# Test.net
KiCad netlist of a schematic drawn in EAGLE
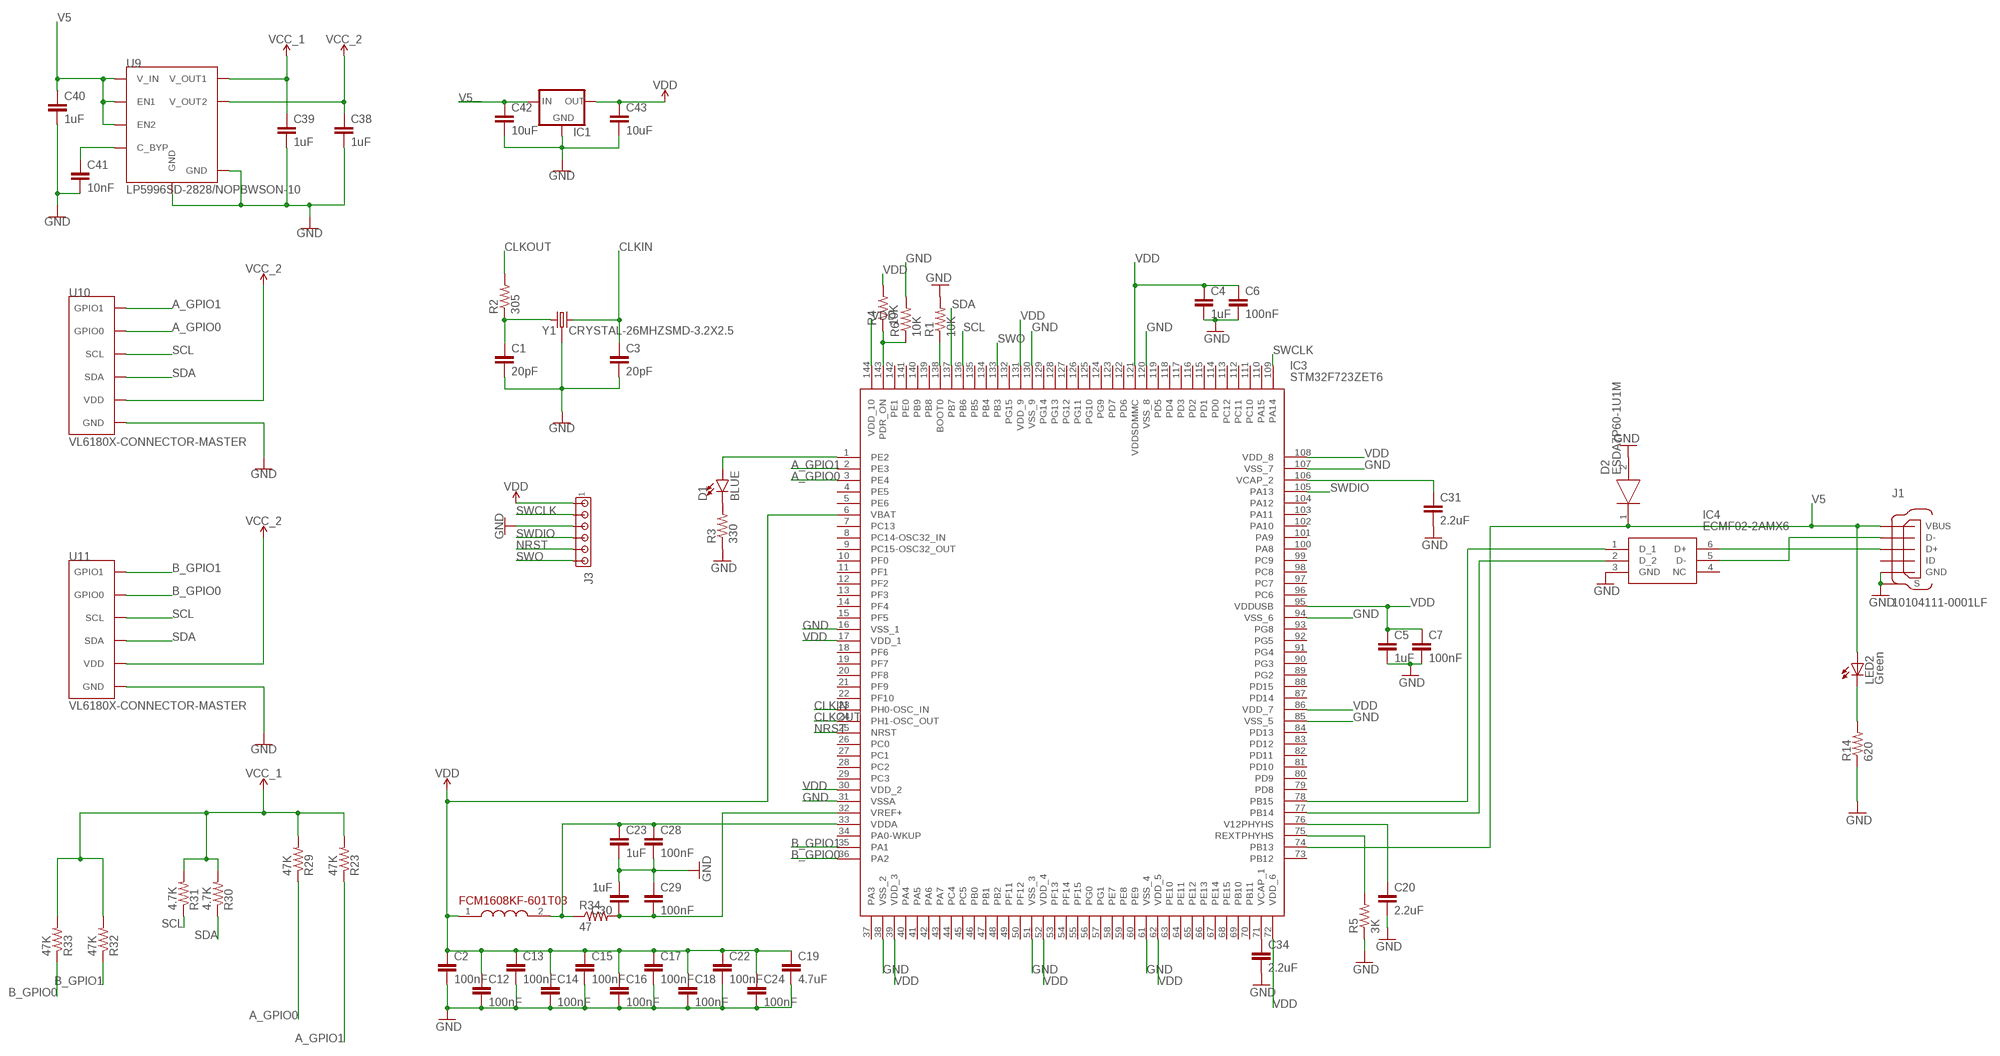
[diagram p0: schematic, sheet 1]

(export (version "E")
  (design (tool "Eeschema 10.0.6"))
  (components
    (comp (ref "C1")
      (value "20pF")
      (footprint "eagle-import:C0603")
      (libsource (lib "eagle-import") (part "C-EUC0603"))
    )
    (comp (ref "C2")
      (value "100nF")
      (footprint "eagle-import:C0603K")
      (libsource (lib "eagle-import") (part "C-EUC0603K"))
    )
    (comp (ref "C3")
      (value "20pF")
      (footprint "eagle-import:C0603")
      (libsource (lib "eagle-import") (part "C-EUC0603"))
    )
    (comp (ref "C4")
      (value "1uF")
      (footprint "eagle-import:C0603K")
      (libsource (lib "eagle-import") (part "C-EUC0603K"))
    )
    (comp (ref "C5")
      (value "1uF")
      (footprint "eagle-import:C0603K")
      (libsource (lib "eagle-import") (part "C-EUC0603K"))
    )
    (comp (ref "C6")
      (value "100nF")
      (footprint "eagle-import:C0603K")
      (libsource (lib "eagle-import") (part "C-EUC0603K"))
    )
    (comp (ref "C7")
      (value "100nF")
      (footprint "eagle-import:C0603K")
      (libsource (lib "eagle-import") (part "C-EUC0603K"))
    )
    (comp (ref "C12")
      (value "100nF")
      (footprint "eagle-import:C0603K")
      (libsource (lib "eagle-import") (part "C-EUC0603K"))
    )
    (comp (ref "C13")
      (value "100nF")
      (footprint "eagle-import:C0603K")
      (libsource (lib "eagle-import") (part "C-EUC0603K"))
    )
    (comp (ref "C14")
      (value "100nF")
      (footprint "eagle-import:C0603K")
      (libsource (lib "eagle-import") (part "C-EUC0603K"))
    )
    (comp (ref "C15")
      (value "100nF")
      (footprint "eagle-import:C0603K")
      (libsource (lib "eagle-import") (part "C-EUC0603K"))
    )
    (comp (ref "C16")
      (value "100nF")
      (footprint "eagle-import:C0603K")
      (libsource (lib "eagle-import") (part "C-EUC0603K"))
    )
    (comp (ref "C17")
      (value "100nF")
      (footprint "eagle-import:C0603K")
      (libsource (lib "eagle-import") (part "C-EUC0603K"))
    )
    (comp (ref "C18")
      (value "100nF")
      (footprint "eagle-import:C0603K")
      (libsource (lib "eagle-import") (part "C-EUC0603K"))
    )
    (comp (ref "C19")
      (value "4.7uF")
      (footprint "eagle-import:C0603K")
      (libsource (lib "eagle-import") (part "C-EUC0603K"))
    )
    (comp (ref "C20")
      (value "2.2uF")
      (footprint "eagle-import:C0603K")
      (libsource (lib "eagle-import") (part "C-EUC0603K"))
    )
    (comp (ref "C22")
      (value "100nF")
      (footprint "eagle-import:C0603K")
      (libsource (lib "eagle-import") (part "C-EUC0603K"))
    )
    (comp (ref "C23")
      (value "1uF")
      (footprint "eagle-import:C0603K")
      (libsource (lib "eagle-import") (part "C-EUC0603K"))
    )
    (comp (ref "C24")
      (value "100nF")
      (footprint "eagle-import:C0603K")
      (libsource (lib "eagle-import") (part "C-EUC0603K"))
    )
    (comp (ref "C28")
      (value "100nF")
      (footprint "eagle-import:C0603K")
      (libsource (lib "eagle-import") (part "C-EUC0603K"))
    )
    (comp (ref "C29")
      (value "100nF")
      (footprint "eagle-import:C0603K")
      (libsource (lib "eagle-import") (part "C-EUC0603K"))
    )
    (comp (ref "C30")
      (value "1uF")
      (footprint "eagle-import:C0603K")
      (libsource (lib "eagle-import") (part "C-EUC0603K"))
    )
    (comp (ref "C31")
      (value "2.2uF")
      (footprint "eagle-import:C0603K")
      (libsource (lib "eagle-import") (part "C-EUC0603K"))
    )
    (comp (ref "C34")
      (value "2.2uF")
      (footprint "eagle-import:C0603K")
      (libsource (lib "eagle-import") (part "C-EUC0603K"))
    )
    (comp (ref "C38")
      (value "1uF")
      (footprint "eagle-import:C0603K")
      (libsource (lib "eagle-import") (part "C-EUC0603K"))
    )
    (comp (ref "C39")
      (value "1uF")
      (footprint "eagle-import:C0603K")
      (libsource (lib "eagle-import") (part "C-EUC0603K"))
    )
    (comp (ref "C40")
      (value "1uF")
      (footprint "eagle-import:C0603K")
      (libsource (lib "eagle-import") (part "C-EUC0603K"))
    )
    (comp (ref "C41")
      (value "10nF")
      (footprint "eagle-import:C0603K")
      (libsource (lib "eagle-import") (part "C-EUC0603K"))
    )
    (comp (ref "C42")
      (value "10uF")
      (footprint "eagle-import:C0603K")
      (libsource (lib "eagle-import") (part "C-EUC0603K"))
    )
    (comp (ref "C43")
      (value "10uF")
      (footprint "eagle-import:C0603K")
      (libsource (lib "eagle-import") (part "C-EUC0603K"))
    )
    (comp (ref "D1")
      (value "BLUE")
      (footprint "eagle-import:LED-0603")
      (libsource (lib "eagle-import") (part "LED-BLUE0603"))
    )
    (comp (ref "D2")
      (value "ESDA7P60-1U1M")
      (footprint "eagle-import:ESDA7P601U1M")
      (fields (field (name "MOUSER_PART_NUMBER") "511-ESDA7P60-1U1M"))
      (libsource (lib "eagle-import") (part "ESDA7P60-1U1M"))
    )
    (comp (ref "FCM1608KF")
      (value "FCM1608KF-601T03")
      (footprint "eagle-import:FCM1608KF-601T03")
      (libsource (lib "eagle-import") (part "FCM1608KF-601T03"))
    )
    (comp (ref "IC1")
      (value "LM1117")
      (footprint "eagle-import:SOT223")
      (libsource (lib "eagle-import") (part "LM1117"))
    )
    (comp (ref "IC3")
      (value "STM32F723ZET6")
      (footprint "eagle-import:QFP50P2200X2200X160-144N")
      (fields (field (name "MOUSER_PART_NUMBER") "511-STM32F723ZET6"))
      (libsource (lib "eagle-import") (part "STM32F723ZET6"))
    )
    (comp (ref "IC4")
      (value "ECMF02-2AMX6")
      (footprint "eagle-import:SON50P150X170X55-6N")
      (fields (field (name "MOUSER_PART_NUMBER") "511-ECMF02-2AMX6"))
      (libsource (lib "eagle-import") (part "ECMF02-2AMX6"))
    )
    (comp (ref "J1")
      (value "10104111-0001LF")
      (footprint "eagle-import:FRAMATOME_10104111-0001LF")
      (fields (field (name "MF") "Amphenol ICC"))
      (libsource (lib "eagle-import") (part "10104111-0001LF"))
    )
    (comp (ref "J3")
      (value "MTA06-100")
      (footprint "eagle-import:10X06MTA")
      (libsource (lib "eagle-import") (part "MTA06-100"))
    )
    (comp (ref "LED2")
      (value "Green")
      (footprint "eagle-import:CHIP-LED0603")
      (libsource (lib "eagle-import") (part "LEDCHIP-LED0603"))
    )
    (comp (ref "R1")
      (value "10K")
      (footprint "eagle-import:R0603")
      (libsource (lib "eagle-import") (part "R-US_R0603"))
    )
    (comp (ref "R2")
      (value "305")
      (footprint "eagle-import:R0603")
      (libsource (lib "eagle-import") (part "R-US_R0603"))
    )
    (comp (ref "R3")
      (value "330")
      (footprint "eagle-import:R0603")
      (libsource (lib "eagle-import") (part "R-US_R0603"))
    )
    (comp (ref "R4")
      (value "10K")
      (footprint "eagle-import:R0603")
      (libsource (lib "eagle-import") (part "R-US_R0603"))
    )
    (comp (ref "R5")
      (value "3K")
      (footprint "eagle-import:R0603")
      (libsource (lib "eagle-import") (part "R-US_R0603"))
    )
    (comp (ref "R6")
      (value "10K")
      (footprint "eagle-import:R0603")
      (libsource (lib "eagle-import") (part "R-US_R0603"))
    )
    (comp (ref "R14")
      (value "620")
      (footprint "eagle-import:R0603")
      (libsource (lib "eagle-import") (part "R-US_R0603"))
    )
    (comp (ref "R23")
      (value "47K")
      (footprint "eagle-import:R0603")
      (libsource (lib "eagle-import") (part "R-US_R0603"))
    )
    (comp (ref "R29")
      (value "47K")
      (footprint "eagle-import:R0603")
      (libsource (lib "eagle-import") (part "R-US_R0603"))
    )
    (comp (ref "R30")
      (value "4.7K")
      (footprint "eagle-import:R0603")
      (libsource (lib "eagle-import") (part "R-US_R0603"))
    )
    (comp (ref "R31")
      (value "4.7K")
      (footprint "eagle-import:R0603")
      (libsource (lib "eagle-import") (part "R-US_R0603"))
    )
    (comp (ref "R32")
      (value "47K")
      (footprint "eagle-import:R0603")
      (libsource (lib "eagle-import") (part "R-US_R0603"))
    )
    (comp (ref "R33")
      (value "47K")
      (footprint "eagle-import:R0603")
      (libsource (lib "eagle-import") (part "R-US_R0603"))
    )
    (comp (ref "R34")
      (value "47")
      (footprint "eagle-import:R0603")
      (libsource (lib "eagle-import") (part "R-US_R0603"))
    )
    (comp (ref "U9")
      (value "LP5996SD-2828/NOPBWSON-10")
      (footprint "eagle-import:WSON-10")
      (libsource (lib "eagle-import") (part "LP5996SD-2828/NOPBWSON-10"))
    )
    (comp (ref "U10")
      (value "VL6180X-CONNECTOR-MASTER")
      (footprint "eagle-import:FH33-6S-0.5SH(10)-MASTER")
      (libsource (lib "eagle-import") (part "VL6180X-CONNECTOR-MASTER"))
    )
    (comp (ref "U11")
      (value "VL6180X-CONNECTOR-MASTER")
      (footprint "eagle-import:FH33-6S-0.5SH(10)-MASTER")
      (libsource (lib "eagle-import") (part "VL6180X-CONNECTOR-MASTER"))
    )
    (comp (ref "Y1")
      (value "CRYSTAL-26MHZSMD-3.2X2.5")
      (footprint "eagle-import:CRYSTAL-SMD-3.2X2.5MM")
      (libsource (lib "eagle-import") (part "CRYSTAL-26MHZSMD-3.2X2.5"))
    )
  )
  (nets
    (net (code "1") (name "/A_GPIO0") (class "Default")
      (node (ref "IC3") (pin "3") (pinfunction "PE4_3") (pintype "bidirectional"))
      (node (ref "R29") (pin "1") (pinfunction "1_1") (pintype "passive"))
      (node (ref "U10") (pin "2") (pinfunction "GPIO0_2") (pintype "bidirectional"))
    )
    (net (code "2") (name "/A_GPIO1") (class "Default")
      (node (ref "IC3") (pin "2") (pinfunction "PE3_2") (pintype "bidirectional"))
      (node (ref "R23") (pin "1") (pinfunction "1_1") (pintype "passive"))
      (node (ref "U10") (pin "1") (pinfunction "GPIO1_1") (pintype "bidirectional"))
    )
    (net (code "3") (name "/B_GPIO0") (class "Default")
      (node (ref "IC3") (pin "36") (pinfunction "PA2_36") (pintype "bidirectional"))
      (node (ref "R33") (pin "1") (pinfunction "1_1") (pintype "passive"))
      (node (ref "U11") (pin "2") (pinfunction "GPIO0_2") (pintype "bidirectional"))
    )
    (net (code "4") (name "/B_GPIO1") (class "Default")
      (node (ref "IC3") (pin "35") (pinfunction "PA1_35") (pintype "bidirectional"))
      (node (ref "R32") (pin "1") (pinfunction "1_1") (pintype "passive"))
      (node (ref "U11") (pin "1") (pinfunction "GPIO1_1") (pintype "bidirectional"))
    )
    (net (code "5") (name "/CLKIN") (class "Default")
      (node (ref "C3") (pin "1") (pinfunction "1_1") (pintype "passive"))
      (node (ref "IC3") (pin "23") (pinfunction "PH0-OSC_IN_23") (pintype "bidirectional"))
      (node (ref "Y1") (pin "3") (pinfunction "2_3") (pintype "passive"))
    )
    (net (code "6") (name "/CLKOUT") (class "Default")
      (node (ref "IC3") (pin "24") (pinfunction "PH1-OSC_OUT_24") (pintype "bidirectional"))
      (node (ref "R2") (pin "2") (pinfunction "2_2") (pintype "passive"))
    )
    (net (code "7") (name "/NRST") (class "Default")
      (node (ref "IC3") (pin "25") (pinfunction "NRST_25") (pintype "bidirectional"))
      (node (ref "J3") (pin "5") (pinfunction "5_5") (pintype "passive"))
    )
    (net (code "8") (name "/SCL") (class "Default")
      (node (ref "IC3") (pin "136") (pinfunction "PB6_136") (pintype "bidirectional"))
      (node (ref "R31") (pin "1") (pinfunction "1_1") (pintype "passive"))
      (node (ref "U10") (pin "3") (pinfunction "SCL_3") (pintype "bidirectional"))
      (node (ref "U11") (pin "3") (pinfunction "SCL_3") (pintype "bidirectional"))
    )
    (net (code "9") (name "/SDA") (class "Default")
      (node (ref "IC3") (pin "137") (pinfunction "PB7_137") (pintype "bidirectional"))
      (node (ref "R30") (pin "1") (pinfunction "1_1") (pintype "passive"))
      (node (ref "U10") (pin "4") (pinfunction "SDA_4") (pintype "bidirectional"))
      (node (ref "U11") (pin "4") (pinfunction "SDA_4") (pintype "bidirectional"))
    )
    (net (code "10") (name "/SWCLK") (class "Default")
      (node (ref "IC3") (pin "109") (pinfunction "PA14_109") (pintype "bidirectional"))
      (node (ref "J3") (pin "2") (pinfunction "2_2") (pintype "passive"))
    )
    (net (code "11") (name "/SWDIO") (class "Default")
      (node (ref "IC3") (pin "105") (pinfunction "PA13_105") (pintype "bidirectional"))
      (node (ref "J3") (pin "4") (pinfunction "4_4") (pintype "passive"))
    )
    (net (code "12") (name "/SWO") (class "Default")
      (node (ref "IC3") (pin "133") (pinfunction "PB3_133") (pintype "bidirectional"))
      (node (ref "J3") (pin "6") (pinfunction "6_6") (pintype "passive"))
    )
    (net (code "13") (name "/V5") (class "Default")
      (node (ref "C40") (pin "1") (pinfunction "1_1") (pintype "passive"))
      (node (ref "C42") (pin "1") (pinfunction "1_1") (pintype "passive"))
      (node (ref "D2") (pin "1") (pinfunction "K_1") (pintype "bidirectional"))
      (node (ref "IC1") (pin "3") (pinfunction "IN_3") (pintype "input"))
      (node (ref "IC3") (pin "74") (pinfunction "PB13_74") (pintype "bidirectional"))
      (node (ref "J1") (pin "1") (pinfunction "VBUS_1") (pintype "power_in"))
      (node (ref "LED2") (pin "A") (pinfunction "A_A") (pintype "passive"))
      (node (ref "U9") (pin "1") (pinfunction "V_IN_1") (pintype "power_in"))
      (node (ref "U9") (pin "2") (pinfunction "EN1_2") (pintype "input"))
      (node (ref "U9") (pin "3") (pinfunction "EN2_3") (pintype "input"))
    )
    (net (code "14") (name "GND") (class "Default")
      (node (ref "C1") (pin "2") (pinfunction "2_2") (pintype "passive"))
      (node (ref "C12") (pin "2") (pinfunction "2_2") (pintype "passive"))
      (node (ref "C13") (pin "2") (pinfunction "2_2") (pintype "passive"))
      (node (ref "C14") (pin "2") (pinfunction "2_2") (pintype "passive"))
      (node (ref "C15") (pin "2") (pinfunction "2_2") (pintype "passive"))
      (node (ref "C16") (pin "2") (pinfunction "2_2") (pintype "passive"))
      (node (ref "C17") (pin "2") (pinfunction "2_2") (pintype "passive"))
      (node (ref "C18") (pin "2") (pinfunction "2_2") (pintype "passive"))
      (node (ref "C19") (pin "2") (pinfunction "2_2") (pintype "passive"))
      (node (ref "C2") (pin "2") (pinfunction "2_2") (pintype "passive"))
      (node (ref "C20") (pin "2") (pinfunction "2_2") (pintype "passive"))
      (node (ref "C22") (pin "2") (pinfunction "2_2") (pintype "passive"))
      (node (ref "C23") (pin "2") (pinfunction "2_2") (pintype "passive"))
      (node (ref "C24") (pin "2") (pinfunction "2_2") (pintype "passive"))
      (node (ref "C28") (pin "2") (pinfunction "2_2") (pintype "passive"))
      (node (ref "C29") (pin "1") (pinfunction "1_1") (pintype "passive"))
      (node (ref "C3") (pin "2") (pinfunction "2_2") (pintype "passive"))
      (node (ref "C30") (pin "2") (pinfunction "2_2") (pintype "passive"))
      (node (ref "C31") (pin "2") (pinfunction "2_2") (pintype "passive"))
      (node (ref "C34") (pin "2") (pinfunction "2_2") (pintype "passive"))
      (node (ref "C38") (pin "2") (pinfunction "2_2") (pintype "passive"))
      (node (ref "C39") (pin "2") (pinfunction "2_2") (pintype "passive"))
      (node (ref "C4") (pin "2") (pinfunction "2_2") (pintype "passive"))
      (node (ref "C40") (pin "2") (pinfunction "2_2") (pintype "passive"))
      (node (ref "C41") (pin "2") (pinfunction "2_2") (pintype "passive"))
      (node (ref "C42") (pin "2") (pinfunction "2_2") (pintype "passive"))
      (node (ref "C43") (pin "2") (pinfunction "2_2") (pintype "passive"))
      (node (ref "C5") (pin "2") (pinfunction "2_2") (pintype "passive"))
      (node (ref "C6") (pin "2") (pinfunction "2_2") (pintype "passive"))
      (node (ref "C7") (pin "2") (pinfunction "2_2") (pintype "passive"))
      (node (ref "D2") (pin "2") (pinfunction "A_2") (pintype "bidirectional"))
      (node (ref "IC1") (pin "1") (pinfunction "GND_1") (pintype "input"))
      (node (ref "IC3") (pin "107") (pinfunction "VSS_7_107") (pintype "power_in"))
      (node (ref "IC3") (pin "120") (pinfunction "VSS_8_120") (pintype "power_in"))
      (node (ref "IC3") (pin "130") (pinfunction "VSS_9_130") (pintype "power_in"))
      (node (ref "IC3") (pin "16") (pinfunction "VSS_1_16") (pintype "power_in"))
      (node (ref "IC3") (pin "31") (pinfunction "VSSA_31") (pintype "power_in"))
      (node (ref "IC3") (pin "38") (pinfunction "VSS_2_38") (pintype "power_in"))
      (node (ref "IC3") (pin "51") (pinfunction "VSS_3_51") (pintype "power_in"))
      (node (ref "IC3") (pin "61") (pinfunction "VSS_4_61") (pintype "power_in"))
      (node (ref "IC3") (pin "85") (pinfunction "VSS_5_85") (pintype "power_in"))
      (node (ref "IC3") (pin "94") (pinfunction "VSS_6_94") (pintype "power_in"))
      (node (ref "IC4") (pin "3") (pinfunction "GND_3") (pintype "bidirectional"))
      (node (ref "J1") (pin "5") (pinfunction "GND_5") (pintype "power_in"))
      (node (ref "J1") (pin "6") (pinfunction "S_6") (pintype "power_in"))
      (node (ref "J1") (pin "7") (pinfunction "S_7") (pintype "power_in"))
      (node (ref "J1") (pin "8") (pinfunction "S_8") (pintype "power_in"))
      (node (ref "J1") (pin "9") (pinfunction "S_9") (pintype "power_in"))
      (node (ref "J3") (pin "3") (pinfunction "3_3") (pintype "passive"))
      (node (ref "R1") (pin "2") (pinfunction "2_2") (pintype "passive"))
      (node (ref "R14") (pin "1") (pinfunction "1_1") (pintype "passive"))
      (node (ref "R3") (pin "1") (pinfunction "1_1") (pintype "passive"))
      (node (ref "R5") (pin "1") (pinfunction "1_1") (pintype "passive"))
      (node (ref "R6") (pin "2") (pinfunction "2_2") (pintype "passive"))
      (node (ref "U10") (pin "6") (pinfunction "GND_6") (pintype "power_in"))
      (node (ref "U11") (pin "6") (pinfunction "GND_6") (pintype "power_in"))
      (node (ref "U9") (pin "11") (pinfunction "GND_11") (pintype "power_in"))
      (node (ref "U9") (pin "6") (pinfunction "GND_6") (pintype "power_in"))
      (node (ref "Y1") (pin "2") (pinfunction "3_2") (pintype "passive"))
      (node (ref "Y1") (pin "4") (pinfunction "3_4") (pintype "passive"))
    )
    (net (code "15") (name "Net-(C1-Pad1)") (class "Default")
      (node (ref "C1") (pin "1") (pinfunction "1_1") (pintype "passive"))
      (node (ref "R2") (pin "1") (pinfunction "1_1") (pintype "passive"))
      (node (ref "Y1") (pin "1") (pinfunction "1_1") (pintype "passive"))
    )
    (net (code "16") (name "Net-(D1-PadC)") (class "Default")
      (node (ref "D1") (pin "C") (pinfunction "C_C") (pintype "passive"))
      (node (ref "R3") (pin "2") (pinfunction "2_2") (pintype "passive"))
    )
    (net (code "17") (name "Net-(FCM1608KF-2.OUT)") (class "Default")
      (node (ref "C23") (pin "1") (pinfunction "1_1") (pintype "passive"))
      (node (ref "C28") (pin "1") (pinfunction "1_1") (pintype "passive"))
      (node (ref "FCM1608KF") (pin "2") (pinfunction "2.OUT_2") (pintype "bidirectional"))
      (node (ref "IC3") (pin "33") (pinfunction "VDDA_33") (pintype "power_in"))
      (node (ref "R34") (pin "1") (pinfunction "1_1") (pintype "passive"))
    )
    (net (code "18") (name "Net-(IC3-BOOT0)") (class "Default")
      (node (ref "IC3") (pin "138") (pinfunction "BOOT0_138") (pintype "bidirectional"))
      (node (ref "R1") (pin "1") (pinfunction "1_1") (pintype "passive"))
    )
    (net (code "19") (name "Net-(IC3-PB14)") (class "Default")
      (node (ref "IC3") (pin "77") (pinfunction "PB14_77") (pintype "bidirectional"))
      (node (ref "IC4") (pin "2") (pinfunction "D_2_2") (pintype "bidirectional"))
    )
    (net (code "20") (name "Net-(IC3-PB15)") (class "Default")
      (node (ref "IC3") (pin "78") (pinfunction "PB15_78") (pintype "bidirectional"))
      (node (ref "IC4") (pin "1") (pinfunction "D_1_1") (pintype "bidirectional"))
    )
    (net (code "21") (name "Net-(IC3-PDR_ON)") (class "Default")
      (node (ref "IC3") (pin "143") (pinfunction "PDR_ON_143") (pintype "bidirectional"))
      (node (ref "R4") (pin "1") (pinfunction "1_1") (pintype "passive"))
      (node (ref "R6") (pin "1") (pinfunction "1_1") (pintype "passive"))
    )
    (net (code "22") (name "Net-(IC3-PE2)") (class "Default")
      (node (ref "D1") (pin "A") (pinfunction "A_A") (pintype "passive"))
      (node (ref "IC3") (pin "1") (pinfunction "PE2_1") (pintype "bidirectional"))
    )
    (net (code "23") (name "Net-(IC3-REXTPHYHS)") (class "Default")
      (node (ref "IC3") (pin "75") (pinfunction "REXTPHYHS_75") (pintype "bidirectional"))
      (node (ref "R5") (pin "2") (pinfunction "2_2") (pintype "passive"))
    )
    (net (code "24") (name "Net-(IC3-V12PHYHS)") (class "Default")
      (node (ref "C20") (pin "1") (pinfunction "1_1") (pintype "passive"))
      (node (ref "IC3") (pin "76") (pinfunction "V12PHYHS_76") (pintype "power_in"))
    )
    (net (code "25") (name "Net-(IC3-VCAP_1)") (class "Default")
      (node (ref "C34") (pin "1") (pinfunction "1_1") (pintype "passive"))
      (node (ref "IC3") (pin "71") (pinfunction "VCAP_1_71") (pintype "power_in"))
    )
    (net (code "26") (name "Net-(IC3-VCAP_2)") (class "Default")
      (node (ref "C31") (pin "1") (pinfunction "1_1") (pintype "passive"))
      (node (ref "IC3") (pin "106") (pinfunction "VCAP_2_106") (pintype "power_in"))
    )
    (net (code "27") (name "Net-(IC3-VREF+)") (class "Default")
      (node (ref "C29") (pin "2") (pinfunction "2_2") (pintype "passive"))
      (node (ref "C30") (pin "1") (pinfunction "1_1") (pintype "passive"))
      (node (ref "IC3") (pin "32") (pinfunction "VREF+_32") (pintype "power_in"))
      (node (ref "R34") (pin "2") (pinfunction "2_2") (pintype "passive"))
    )
    (net (code "28") (name "Net-(IC4-D+)") (class "Default")
      (node (ref "IC4") (pin "6") (pinfunction "D+_6") (pintype "bidirectional"))
      (node (ref "J1") (pin "3") (pinfunction "D+_3") (pintype "passive"))
    )
    (net (code "29") (name "Net-(IC4-D-)") (class "Default")
      (node (ref "IC4") (pin "5") (pinfunction "D-_5") (pintype "bidirectional"))
      (node (ref "J1") (pin "2") (pinfunction "D-_2") (pintype "passive"))
    )
    (net (code "30") (name "Net-(LED2-PadC)") (class "Default")
      (node (ref "LED2") (pin "C") (pinfunction "C_C") (pintype "passive"))
      (node (ref "R14") (pin "2") (pinfunction "2_2") (pintype "passive"))
    )
    (net (code "31") (name "Net-(U9-C_BYP)") (class "Default")
      (node (ref "C41") (pin "1") (pinfunction "1_1") (pintype "passive"))
      (node (ref "U9") (pin "4") (pinfunction "C_BYP_4") (pintype "power_in"))
    )
    (net (code "32") (name "VCC_1") (class "Default")
      (node (ref "C39") (pin "1") (pinfunction "1_1") (pintype "passive"))
      (node (ref "R23") (pin "2") (pinfunction "2_2") (pintype "passive"))
      (node (ref "R29") (pin "2") (pinfunction "2_2") (pintype "passive"))
      (node (ref "R30") (pin "2") (pinfunction "2_2") (pintype "passive"))
      (node (ref "R31") (pin "2") (pinfunction "2_2") (pintype "passive"))
      (node (ref "R32") (pin "2") (pinfunction "2_2") (pintype "passive"))
      (node (ref "R33") (pin "2") (pinfunction "2_2") (pintype "passive"))
      (node (ref "U9") (pin "10") (pinfunction "V_OUT1_10") (pintype "power_in"))
    )
    (net (code "33") (name "VCC_2") (class "Default")
      (node (ref "C38") (pin "1") (pinfunction "1_1") (pintype "passive"))
      (node (ref "U10") (pin "5") (pinfunction "VDD_5") (pintype "power_in"))
      (node (ref "U11") (pin "5") (pinfunction "VDD_5") (pintype "power_in"))
      (node (ref "U9") (pin "9") (pinfunction "V_OUT2_9") (pintype "power_in"))
    )
    (net (code "34") (name "VDD") (class "Default")
      (node (ref "C12") (pin "1") (pinfunction "1_1") (pintype "passive"))
      (node (ref "C13") (pin "1") (pinfunction "1_1") (pintype "passive"))
      (node (ref "C14") (pin "1") (pinfunction "1_1") (pintype "passive"))
      (node (ref "C15") (pin "1") (pinfunction "1_1") (pintype "passive"))
      (node (ref "C16") (pin "1") (pinfunction "1_1") (pintype "passive"))
      (node (ref "C17") (pin "1") (pinfunction "1_1") (pintype "passive"))
      (node (ref "C18") (pin "1") (pinfunction "1_1") (pintype "passive"))
      (node (ref "C19") (pin "1") (pinfunction "1_1") (pintype "passive"))
      (node (ref "C2") (pin "1") (pinfunction "1_1") (pintype "passive"))
      (node (ref "C22") (pin "1") (pinfunction "1_1") (pintype "passive"))
      (node (ref "C24") (pin "1") (pinfunction "1_1") (pintype "passive"))
      (node (ref "C4") (pin "1") (pinfunction "1_1") (pintype "passive"))
      (node (ref "C43") (pin "1") (pinfunction "1_1") (pintype "passive"))
      (node (ref "C5") (pin "1") (pinfunction "1_1") (pintype "passive"))
      (node (ref "C6") (pin "1") (pinfunction "1_1") (pintype "passive"))
      (node (ref "C7") (pin "1") (pinfunction "1_1") (pintype "passive"))
      (node (ref "FCM1608KF") (pin "1") (pinfunction "1.IN_1") (pintype "bidirectional"))
      (node (ref "IC1") (pin "2") (pinfunction "OUT_2") (pintype "passive"))
      (node (ref "IC3") (pin "108") (pinfunction "VDD_8_108") (pintype "power_in"))
      (node (ref "IC3") (pin "121") (pinfunction "VDDSDMMC_121") (pintype "power_in"))
      (node (ref "IC3") (pin "131") (pinfunction "VDD_9_131") (pintype "power_in"))
      (node (ref "IC3") (pin "144") (pinfunction "VDD_10_144") (pintype "power_in"))
      (node (ref "IC3") (pin "17") (pinfunction "VDD_1_17") (pintype "power_in"))
      (node (ref "IC3") (pin "30") (pinfunction "VDD_2_30") (pintype "power_in"))
      (node (ref "IC3") (pin "39") (pinfunction "VDD_3_39") (pintype "power_in"))
      (node (ref "IC3") (pin "52") (pinfunction "VDD_4_52") (pintype "power_in"))
      (node (ref "IC3") (pin "6") (pinfunction "VBAT_6") (pintype "power_in"))
      (node (ref "IC3") (pin "62") (pinfunction "VDD_5_62") (pintype "power_in"))
      (node (ref "IC3") (pin "72") (pinfunction "VDD_6_72") (pintype "power_in"))
      (node (ref "IC3") (pin "86") (pinfunction "VDD_7_86") (pintype "power_in"))
      (node (ref "IC3") (pin "95") (pinfunction "VDDUSB_95") (pintype "power_in"))
      (node (ref "J3") (pin "1") (pinfunction "1_1") (pintype "passive"))
      (node (ref "R4") (pin "2") (pinfunction "2_2") (pintype "passive"))
    )
    (net (code "35") (name "unconnected-(IC3-PA0-WKUP-Pad34)") (class "Default")
      (node (ref "IC3") (pin "34") (pinfunction "PA0-WKUP_34") (pintype "bidirectional"))
    )
    (net (code "36") (name "unconnected-(IC3-PA3-Pad37)") (class "Default")
      (node (ref "IC3") (pin "37") (pinfunction "PA3_37") (pintype "bidirectional"))
    )
    (net (code "37") (name "unconnected-(IC3-PA4-Pad40)") (class "Default")
      (node (ref "IC3") (pin "40") (pinfunction "PA4_40") (pintype "bidirectional"))
    )
    (net (code "38") (name "unconnected-(IC3-PA5-Pad41)") (class "Default")
      (node (ref "IC3") (pin "41") (pinfunction "PA5_41") (pintype "bidirectional"))
    )
    (net (code "39") (name "unconnected-(IC3-PA6-Pad42)") (class "Default")
      (node (ref "IC3") (pin "42") (pinfunction "PA6_42") (pintype "bidirectional"))
    )
    (net (code "40") (name "unconnected-(IC3-PA7-Pad43)") (class "Default")
      (node (ref "IC3") (pin "43") (pinfunction "PA7_43") (pintype "bidirectional"))
    )
    (net (code "41") (name "unconnected-(IC3-PA8-Pad100)") (class "Default")
      (node (ref "IC3") (pin "100") (pinfunction "PA8_100") (pintype "bidirectional"))
    )
    (net (code "42") (name "unconnected-(IC3-PA9-Pad101)") (class "Default")
      (node (ref "IC3") (pin "101") (pinfunction "PA9_101") (pintype "bidirectional"))
    )
    (net (code "43") (name "unconnected-(IC3-PA10-Pad102)") (class "Default")
      (node (ref "IC3") (pin "102") (pinfunction "PA10_102") (pintype "bidirectional"))
    )
    (net (code "44") (name "unconnected-(IC3-PA11-Pad103)") (class "Default")
      (node (ref "IC3") (pin "103") (pinfunction "PA11_103") (pintype "bidirectional"))
    )
    (net (code "45") (name "unconnected-(IC3-PA12-Pad104)") (class "Default")
      (node (ref "IC3") (pin "104") (pinfunction "PA12_104") (pintype "bidirectional"))
    )
    (net (code "46") (name "unconnected-(IC3-PA15-Pad110)") (class "Default")
      (node (ref "IC3") (pin "110") (pinfunction "PA15_110") (pintype "bidirectional"))
    )
    (net (code "47") (name "unconnected-(IC3-PB0-Pad46)") (class "Default")
      (node (ref "IC3") (pin "46") (pinfunction "PB0_46") (pintype "bidirectional"))
    )
    (net (code "48") (name "unconnected-(IC3-PB1-Pad47)") (class "Default")
      (node (ref "IC3") (pin "47") (pinfunction "PB1_47") (pintype "bidirectional"))
    )
    (net (code "49") (name "unconnected-(IC3-PB2-Pad48)") (class "Default")
      (node (ref "IC3") (pin "48") (pinfunction "PB2_48") (pintype "bidirectional"))
    )
    (net (code "50") (name "unconnected-(IC3-PB4-Pad134)") (class "Default")
      (node (ref "IC3") (pin "134") (pinfunction "PB4_134") (pintype "bidirectional"))
    )
    (net (code "51") (name "unconnected-(IC3-PB5-Pad135)") (class "Default")
      (node (ref "IC3") (pin "135") (pinfunction "PB5_135") (pintype "bidirectional"))
    )
    (net (code "52") (name "unconnected-(IC3-PB8-Pad139)") (class "Default")
      (node (ref "IC3") (pin "139") (pinfunction "PB8_139") (pintype "bidirectional"))
    )
    (net (code "53") (name "unconnected-(IC3-PB9-Pad140)") (class "Default")
      (node (ref "IC3") (pin "140") (pinfunction "PB9_140") (pintype "bidirectional"))
    )
    (net (code "54") (name "unconnected-(IC3-PB10-Pad69)") (class "Default")
      (node (ref "IC3") (pin "69") (pinfunction "PB10_69") (pintype "bidirectional"))
    )
    (net (code "55") (name "unconnected-(IC3-PB11-Pad70)") (class "Default")
      (node (ref "IC3") (pin "70") (pinfunction "PB11_70") (pintype "bidirectional"))
    )
    (net (code "56") (name "unconnected-(IC3-PB12-Pad73)") (class "Default")
      (node (ref "IC3") (pin "73") (pinfunction "PB12_73") (pintype "bidirectional"))
    )
    (net (code "57") (name "unconnected-(IC3-PC0-Pad26)") (class "Default")
      (node (ref "IC3") (pin "26") (pinfunction "PC0_26") (pintype "bidirectional"))
    )
    (net (code "58") (name "unconnected-(IC3-PC1-Pad27)") (class "Default")
      (node (ref "IC3") (pin "27") (pinfunction "PC1_27") (pintype "bidirectional"))
    )
    (net (code "59") (name "unconnected-(IC3-PC2-Pad28)") (class "Default")
      (node (ref "IC3") (pin "28") (pinfunction "PC2_28") (pintype "bidirectional"))
    )
    (net (code "60") (name "unconnected-(IC3-PC3-Pad29)") (class "Default")
      (node (ref "IC3") (pin "29") (pinfunction "PC3_29") (pintype "bidirectional"))
    )
    (net (code "61") (name "unconnected-(IC3-PC4-Pad44)") (class "Default")
      (node (ref "IC3") (pin "44") (pinfunction "PC4_44") (pintype "bidirectional"))
    )
    (net (code "62") (name "unconnected-(IC3-PC5-Pad45)") (class "Default")
      (node (ref "IC3") (pin "45") (pinfunction "PC5_45") (pintype "bidirectional"))
    )
    (net (code "63") (name "unconnected-(IC3-PC6-Pad96)") (class "Default")
      (node (ref "IC3") (pin "96") (pinfunction "PC6_96") (pintype "bidirectional"))
    )
    (net (code "64") (name "unconnected-(IC3-PC7-Pad97)") (class "Default")
      (node (ref "IC3") (pin "97") (pinfunction "PC7_97") (pintype "bidirectional"))
    )
    (net (code "65") (name "unconnected-(IC3-PC8-Pad98)") (class "Default")
      (node (ref "IC3") (pin "98") (pinfunction "PC8_98") (pintype "bidirectional"))
    )
    (net (code "66") (name "unconnected-(IC3-PC9-Pad99)") (class "Default")
      (node (ref "IC3") (pin "99") (pinfunction "PC9_99") (pintype "bidirectional"))
    )
    (net (code "67") (name "unconnected-(IC3-PC10-Pad111)") (class "Default")
      (node (ref "IC3") (pin "111") (pinfunction "PC10_111") (pintype "bidirectional"))
    )
    (net (code "68") (name "unconnected-(IC3-PC11-Pad112)") (class "Default")
      (node (ref "IC3") (pin "112") (pinfunction "PC11_112") (pintype "bidirectional"))
    )
    (net (code "69") (name "unconnected-(IC3-PC12-Pad113)") (class "Default")
      (node (ref "IC3") (pin "113") (pinfunction "PC12_113") (pintype "bidirectional"))
    )
    (net (code "70") (name "unconnected-(IC3-PC13-Pad7)") (class "Default")
      (node (ref "IC3") (pin "7") (pinfunction "PC13_7") (pintype "bidirectional"))
    )
    (net (code "71") (name "unconnected-(IC3-PC14-OSC32_IN-Pad8)") (class "Default")
      (node (ref "IC3") (pin "8") (pinfunction "PC14-OSC32_IN_8") (pintype "bidirectional"))
    )
    (net (code "72") (name "unconnected-(IC3-PC15-OSC32_OUT-Pad9)") (class "Default")
      (node (ref "IC3") (pin "9") (pinfunction "PC15-OSC32_OUT_9") (pintype "bidirectional"))
    )
    (net (code "73") (name "unconnected-(IC3-PD0-Pad114)") (class "Default")
      (node (ref "IC3") (pin "114") (pinfunction "PD0_114") (pintype "bidirectional"))
    )
    (net (code "74") (name "unconnected-(IC3-PD1-Pad115)") (class "Default")
      (node (ref "IC3") (pin "115") (pinfunction "PD1_115") (pintype "bidirectional"))
    )
    (net (code "75") (name "unconnected-(IC3-PD2-Pad116)") (class "Default")
      (node (ref "IC3") (pin "116") (pinfunction "PD2_116") (pintype "bidirectional"))
    )
    (net (code "76") (name "unconnected-(IC3-PD3-Pad117)") (class "Default")
      (node (ref "IC3") (pin "117") (pinfunction "PD3_117") (pintype "bidirectional"))
    )
    (net (code "77") (name "unconnected-(IC3-PD4-Pad118)") (class "Default")
      (node (ref "IC3") (pin "118") (pinfunction "PD4_118") (pintype "bidirectional"))
    )
    (net (code "78") (name "unconnected-(IC3-PD5-Pad119)") (class "Default")
      (node (ref "IC3") (pin "119") (pinfunction "PD5_119") (pintype "bidirectional"))
    )
    (net (code "79") (name "unconnected-(IC3-PD6-Pad122)") (class "Default")
      (node (ref "IC3") (pin "122") (pinfunction "PD6_122") (pintype "bidirectional"))
    )
    (net (code "80") (name "unconnected-(IC3-PD7-Pad123)") (class "Default")
      (node (ref "IC3") (pin "123") (pinfunction "PD7_123") (pintype "bidirectional"))
    )
    (net (code "81") (name "unconnected-(IC3-PD8-Pad79)") (class "Default")
      (node (ref "IC3") (pin "79") (pinfunction "PD8_79") (pintype "bidirectional"))
    )
    (net (code "82") (name "unconnected-(IC3-PD9-Pad80)") (class "Default")
      (node (ref "IC3") (pin "80") (pinfunction "PD9_80") (pintype "bidirectional"))
    )
    (net (code "83") (name "unconnected-(IC3-PD10-Pad81)") (class "Default")
      (node (ref "IC3") (pin "81") (pinfunction "PD10_81") (pintype "bidirectional"))
    )
    (net (code "84") (name "unconnected-(IC3-PD11-Pad82)") (class "Default")
      (node (ref "IC3") (pin "82") (pinfunction "PD11_82") (pintype "bidirectional"))
    )
    (net (code "85") (name "unconnected-(IC3-PD12-Pad83)") (class "Default")
      (node (ref "IC3") (pin "83") (pinfunction "PD12_83") (pintype "bidirectional"))
    )
    (net (code "86") (name "unconnected-(IC3-PD13-Pad84)") (class "Default")
      (node (ref "IC3") (pin "84") (pinfunction "PD13_84") (pintype "bidirectional"))
    )
    (net (code "87") (name "unconnected-(IC3-PD14-Pad87)") (class "Default")
      (node (ref "IC3") (pin "87") (pinfunction "PD14_87") (pintype "bidirectional"))
    )
    (net (code "88") (name "unconnected-(IC3-PD15-Pad88)") (class "Default")
      (node (ref "IC3") (pin "88") (pinfunction "PD15_88") (pintype "bidirectional"))
    )
    (net (code "89") (name "unconnected-(IC3-PE0-Pad141)") (class "Default")
      (node (ref "IC3") (pin "141") (pinfunction "PE0_141") (pintype "bidirectional"))
    )
    (net (code "90") (name "unconnected-(IC3-PE1-Pad142)") (class "Default")
      (node (ref "IC3") (pin "142") (pinfunction "PE1_142") (pintype "bidirectional"))
    )
    (net (code "91") (name "unconnected-(IC3-PE5-Pad4)") (class "Default")
      (node (ref "IC3") (pin "4") (pinfunction "PE5_4") (pintype "bidirectional"))
    )
    (net (code "92") (name "unconnected-(IC3-PE6-Pad5)") (class "Default")
      (node (ref "IC3") (pin "5") (pinfunction "PE6_5") (pintype "bidirectional"))
    )
    (net (code "93") (name "unconnected-(IC3-PE7-Pad58)") (class "Default")
      (node (ref "IC3") (pin "58") (pinfunction "PE7_58") (pintype "bidirectional"))
    )
    (net (code "94") (name "unconnected-(IC3-PE8-Pad59)") (class "Default")
      (node (ref "IC3") (pin "59") (pinfunction "PE8_59") (pintype "bidirectional"))
    )
    (net (code "95") (name "unconnected-(IC3-PE9-Pad60)") (class "Default")
      (node (ref "IC3") (pin "60") (pinfunction "PE9_60") (pintype "bidirectional"))
    )
    (net (code "96") (name "unconnected-(IC3-PE10-Pad63)") (class "Default")
      (node (ref "IC3") (pin "63") (pinfunction "PE10_63") (pintype "bidirectional"))
    )
    (net (code "97") (name "unconnected-(IC3-PE11-Pad64)") (class "Default")
      (node (ref "IC3") (pin "64") (pinfunction "PE11_64") (pintype "bidirectional"))
    )
    (net (code "98") (name "unconnected-(IC3-PE12-Pad65)") (class "Default")
      (node (ref "IC3") (pin "65") (pinfunction "PE12_65") (pintype "bidirectional"))
    )
    (net (code "99") (name "unconnected-(IC3-PE13-Pad66)") (class "Default")
      (node (ref "IC3") (pin "66") (pinfunction "PE13_66") (pintype "bidirectional"))
    )
    (net (code "100") (name "unconnected-(IC3-PE14-Pad67)") (class "Default")
      (node (ref "IC3") (pin "67") (pinfunction "PE14_67") (pintype "bidirectional"))
    )
    (net (code "101") (name "unconnected-(IC3-PE15-Pad68)") (class "Default")
      (node (ref "IC3") (pin "68") (pinfunction "PE15_68") (pintype "bidirectional"))
    )
    (net (code "102") (name "unconnected-(IC3-PF0-Pad10)") (class "Default")
      (node (ref "IC3") (pin "10") (pinfunction "PF0_10") (pintype "bidirectional"))
    )
    (net (code "103") (name "unconnected-(IC3-PF1-Pad11)") (class "Default")
      (node (ref "IC3") (pin "11") (pinfunction "PF1_11") (pintype "bidirectional"))
    )
    (net (code "104") (name "unconnected-(IC3-PF2-Pad12)") (class "Default")
      (node (ref "IC3") (pin "12") (pinfunction "PF2_12") (pintype "bidirectional"))
    )
    (net (code "105") (name "unconnected-(IC3-PF3-Pad13)") (class "Default")
      (node (ref "IC3") (pin "13") (pinfunction "PF3_13") (pintype "bidirectional"))
    )
    (net (code "106") (name "unconnected-(IC3-PF4-Pad14)") (class "Default")
      (node (ref "IC3") (pin "14") (pinfunction "PF4_14") (pintype "bidirectional"))
    )
    (net (code "107") (name "unconnected-(IC3-PF5-Pad15)") (class "Default")
      (node (ref "IC3") (pin "15") (pinfunction "PF5_15") (pintype "bidirectional"))
    )
    (net (code "108") (name "unconnected-(IC3-PF6-Pad18)") (class "Default")
      (node (ref "IC3") (pin "18") (pinfunction "PF6_18") (pintype "bidirectional"))
    )
    (net (code "109") (name "unconnected-(IC3-PF7-Pad19)") (class "Default")
      (node (ref "IC3") (pin "19") (pinfunction "PF7_19") (pintype "bidirectional"))
    )
    (net (code "110") (name "unconnected-(IC3-PF8-Pad20)") (class "Default")
      (node (ref "IC3") (pin "20") (pinfunction "PF8_20") (pintype "bidirectional"))
    )
    (net (code "111") (name "unconnected-(IC3-PF9-Pad21)") (class "Default")
      (node (ref "IC3") (pin "21") (pinfunction "PF9_21") (pintype "bidirectional"))
    )
    (net (code "112") (name "unconnected-(IC3-PF10-Pad22)") (class "Default")
      (node (ref "IC3") (pin "22") (pinfunction "PF10_22") (pintype "bidirectional"))
    )
    (net (code "113") (name "unconnected-(IC3-PF11-Pad49)") (class "Default")
      (node (ref "IC3") (pin "49") (pinfunction "PF11_49") (pintype "bidirectional"))
    )
    (net (code "114") (name "unconnected-(IC3-PF12-Pad50)") (class "Default")
      (node (ref "IC3") (pin "50") (pinfunction "PF12_50") (pintype "bidirectional"))
    )
    (net (code "115") (name "unconnected-(IC3-PF13-Pad53)") (class "Default")
      (node (ref "IC3") (pin "53") (pinfunction "PF13_53") (pintype "bidirectional"))
    )
    (net (code "116") (name "unconnected-(IC3-PF14-Pad54)") (class "Default")
      (node (ref "IC3") (pin "54") (pinfunction "PF14_54") (pintype "bidirectional"))
    )
    (net (code "117") (name "unconnected-(IC3-PF15-Pad55)") (class "Default")
      (node (ref "IC3") (pin "55") (pinfunction "PF15_55") (pintype "bidirectional"))
    )
    (net (code "118") (name "unconnected-(IC3-PG0-Pad56)") (class "Default")
      (node (ref "IC3") (pin "56") (pinfunction "PG0_56") (pintype "bidirectional"))
    )
    (net (code "119") (name "unconnected-(IC3-PG1-Pad57)") (class "Default")
      (node (ref "IC3") (pin "57") (pinfunction "PG1_57") (pintype "bidirectional"))
    )
    (net (code "120") (name "unconnected-(IC3-PG2-Pad89)") (class "Default")
      (node (ref "IC3") (pin "89") (pinfunction "PG2_89") (pintype "bidirectional"))
    )
    (net (code "121") (name "unconnected-(IC3-PG3-Pad90)") (class "Default")
      (node (ref "IC3") (pin "90") (pinfunction "PG3_90") (pintype "bidirectional"))
    )
    (net (code "122") (name "unconnected-(IC3-PG4-Pad91)") (class "Default")
      (node (ref "IC3") (pin "91") (pinfunction "PG4_91") (pintype "bidirectional"))
    )
    (net (code "123") (name "unconnected-(IC3-PG5-Pad92)") (class "Default")
      (node (ref "IC3") (pin "92") (pinfunction "PG5_92") (pintype "bidirectional"))
    )
    (net (code "124") (name "unconnected-(IC3-PG8-Pad93)") (class "Default")
      (node (ref "IC3") (pin "93") (pinfunction "PG8_93") (pintype "bidirectional"))
    )
    (net (code "125") (name "unconnected-(IC3-PG9-Pad124)") (class "Default")
      (node (ref "IC3") (pin "124") (pinfunction "PG9_124") (pintype "bidirectional"))
    )
    (net (code "126") (name "unconnected-(IC3-PG10-Pad125)") (class "Default")
      (node (ref "IC3") (pin "125") (pinfunction "PG10_125") (pintype "bidirectional"))
    )
    (net (code "127") (name "unconnected-(IC3-PG11-Pad126)") (class "Default")
      (node (ref "IC3") (pin "126") (pinfunction "PG11_126") (pintype "bidirectional"))
    )
    (net (code "128") (name "unconnected-(IC3-PG12-Pad127)") (class "Default")
      (node (ref "IC3") (pin "127") (pinfunction "PG12_127") (pintype "bidirectional"))
    )
    (net (code "129") (name "unconnected-(IC3-PG13-Pad128)") (class "Default")
      (node (ref "IC3") (pin "128") (pinfunction "PG13_128") (pintype "bidirectional"))
    )
    (net (code "130") (name "unconnected-(IC3-PG14-Pad129)") (class "Default")
      (node (ref "IC3") (pin "129") (pinfunction "PG14_129") (pintype "bidirectional"))
    )
    (net (code "131") (name "unconnected-(IC3-PG15-Pad132)") (class "Default")
      (node (ref "IC3") (pin "132") (pinfunction "PG15_132") (pintype "bidirectional"))
    )
    (net (code "132") (name "unconnected-(IC4-NC-Pad4)") (class "Default")
      (node (ref "IC4") (pin "4") (pinfunction "NC_4") (pintype "no_connect"))
    )
    (net (code "133") (name "unconnected-(J1-ID-Pad4)") (class "Default")
      (node (ref "J1") (pin "4") (pinfunction "ID_4") (pintype "passive"))
    )
  )
)
